# I2C_header.net
KiCad netlist of a schematic drawn in EAGLE
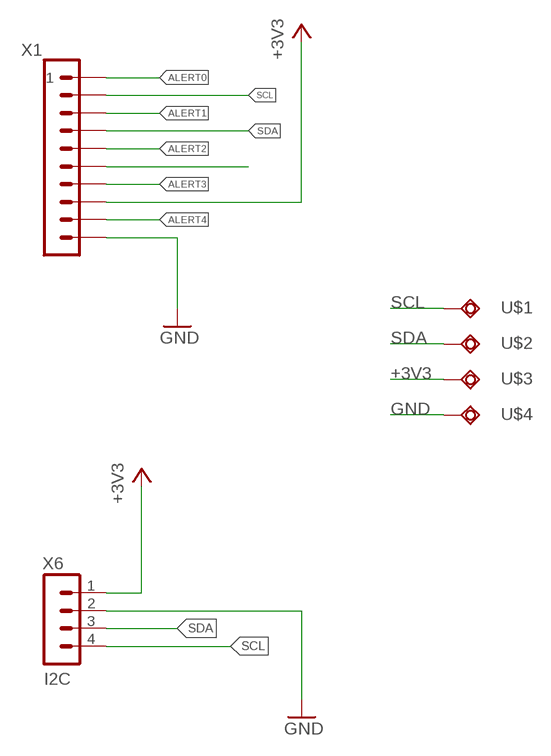
[diagram p0: schematic, sheet 1]

(export (version "E")
  (design (tool "Eeschema 10.0.6"))
  (components
    (comp (ref "U$1")
      (value "PAD3.0X5.0")
      (footprint "eagle-import:PAD3X5")
      (libsource (lib "eagle-import") (part "PAD3.0X5.0"))
    )
    (comp (ref "U$2")
      (value "PAD3.0X5.0")
      (footprint "eagle-import:PAD3X5")
      (libsource (lib "eagle-import") (part "PAD3.0X5.0"))
    )
    (comp (ref "U$3")
      (value "PAD3.0X5.0")
      (footprint "eagle-import:PAD3X5")
      (libsource (lib "eagle-import") (part "PAD3.0X5.0"))
    )
    (comp (ref "U$4")
      (value "PAD3.0X5.0")
      (footprint "eagle-import:PAD3X5")
      (libsource (lib "eagle-import") (part "PAD3.0X5.0"))
    )
    (comp (ref "X1")
      (value "FFC_10PLARGE")
      (footprint "eagle-import:FFC_1.0X10_LARGE_PADS")
      (libsource (lib "eagle-import") (part "FFC_10PLARGE"))
    )
    (comp (ref "X6")
      (value "I2C")
      (footprint "eagle-import:JST-PH_4")
      (libsource (lib "eagle-import") (part "JST04_PH"))
    )
  )
  (nets
    (net (code "1") (name "+3V3") (class "Default")
      (node (ref "U$3") (pin "P$1") (pinfunction "P$1_P$1") (pintype "bidirectional"))
      (node (ref "X1") (pin "P$8") (pinfunction "8_P$8") (pintype "passive"))
      (node (ref "X6") (pin "1") (pinfunction "1_1") (pintype "passive"))
    )
    (net (code "2") (name "ALERT0") (class "Default")
      (node (ref "X1") (pin "P$1") (pinfunction "1_P$1") (pintype "passive"))
    )
    (net (code "3") (name "ALERT1") (class "Default")
      (node (ref "X1") (pin "P$3") (pinfunction "3_P$3") (pintype "passive"))
    )
    (net (code "4") (name "ALERT2") (class "Default")
      (node (ref "X1") (pin "P$5") (pinfunction "5_P$5") (pintype "passive"))
    )
    (net (code "5") (name "ALERT3") (class "Default")
      (node (ref "X1") (pin "P$7") (pinfunction "7_P$7") (pintype "passive"))
    )
    (net (code "6") (name "ALERT4") (class "Default")
      (node (ref "X1") (pin "P$9") (pinfunction "9_P$9") (pintype "passive"))
    )
    (net (code "7") (name "GND") (class "Default")
      (node (ref "U$4") (pin "P$1") (pinfunction "P$1_P$1") (pintype "bidirectional"))
      (node (ref "X1") (pin "P$10") (pinfunction "10_P$10") (pintype "passive"))
      (node (ref "X6") (pin "2") (pinfunction "2_2") (pintype "passive"))
    )
    (net (code "8") (name "SCL") (class "Default")
      (node (ref "U$1") (pin "P$1") (pinfunction "P$1_P$1") (pintype "bidirectional"))
      (node (ref "X1") (pin "P$2") (pinfunction "2_P$2") (pintype "passive"))
      (node (ref "X6") (pin "4") (pinfunction "4_4") (pintype "passive"))
    )
    (net (code "9") (name "SDA") (class "Default")
      (node (ref "U$2") (pin "P$1") (pinfunction "P$1_P$1") (pintype "bidirectional"))
      (node (ref "X1") (pin "P$4") (pinfunction "4_P$4") (pintype "passive"))
      (node (ref "X6") (pin "3") (pinfunction "3_3") (pintype "passive"))
    )
    (net (code "10") (name "unconnected-(X1A-6-PadP$6)") (class "Default")
      (node (ref "X1") (pin "P$6") (pinfunction "6_P$6") (pintype "passive"))
    )
  )
)
